# Quad_FC_V10_0.net
KiCad netlist of a schematic drawn in Altium Designer
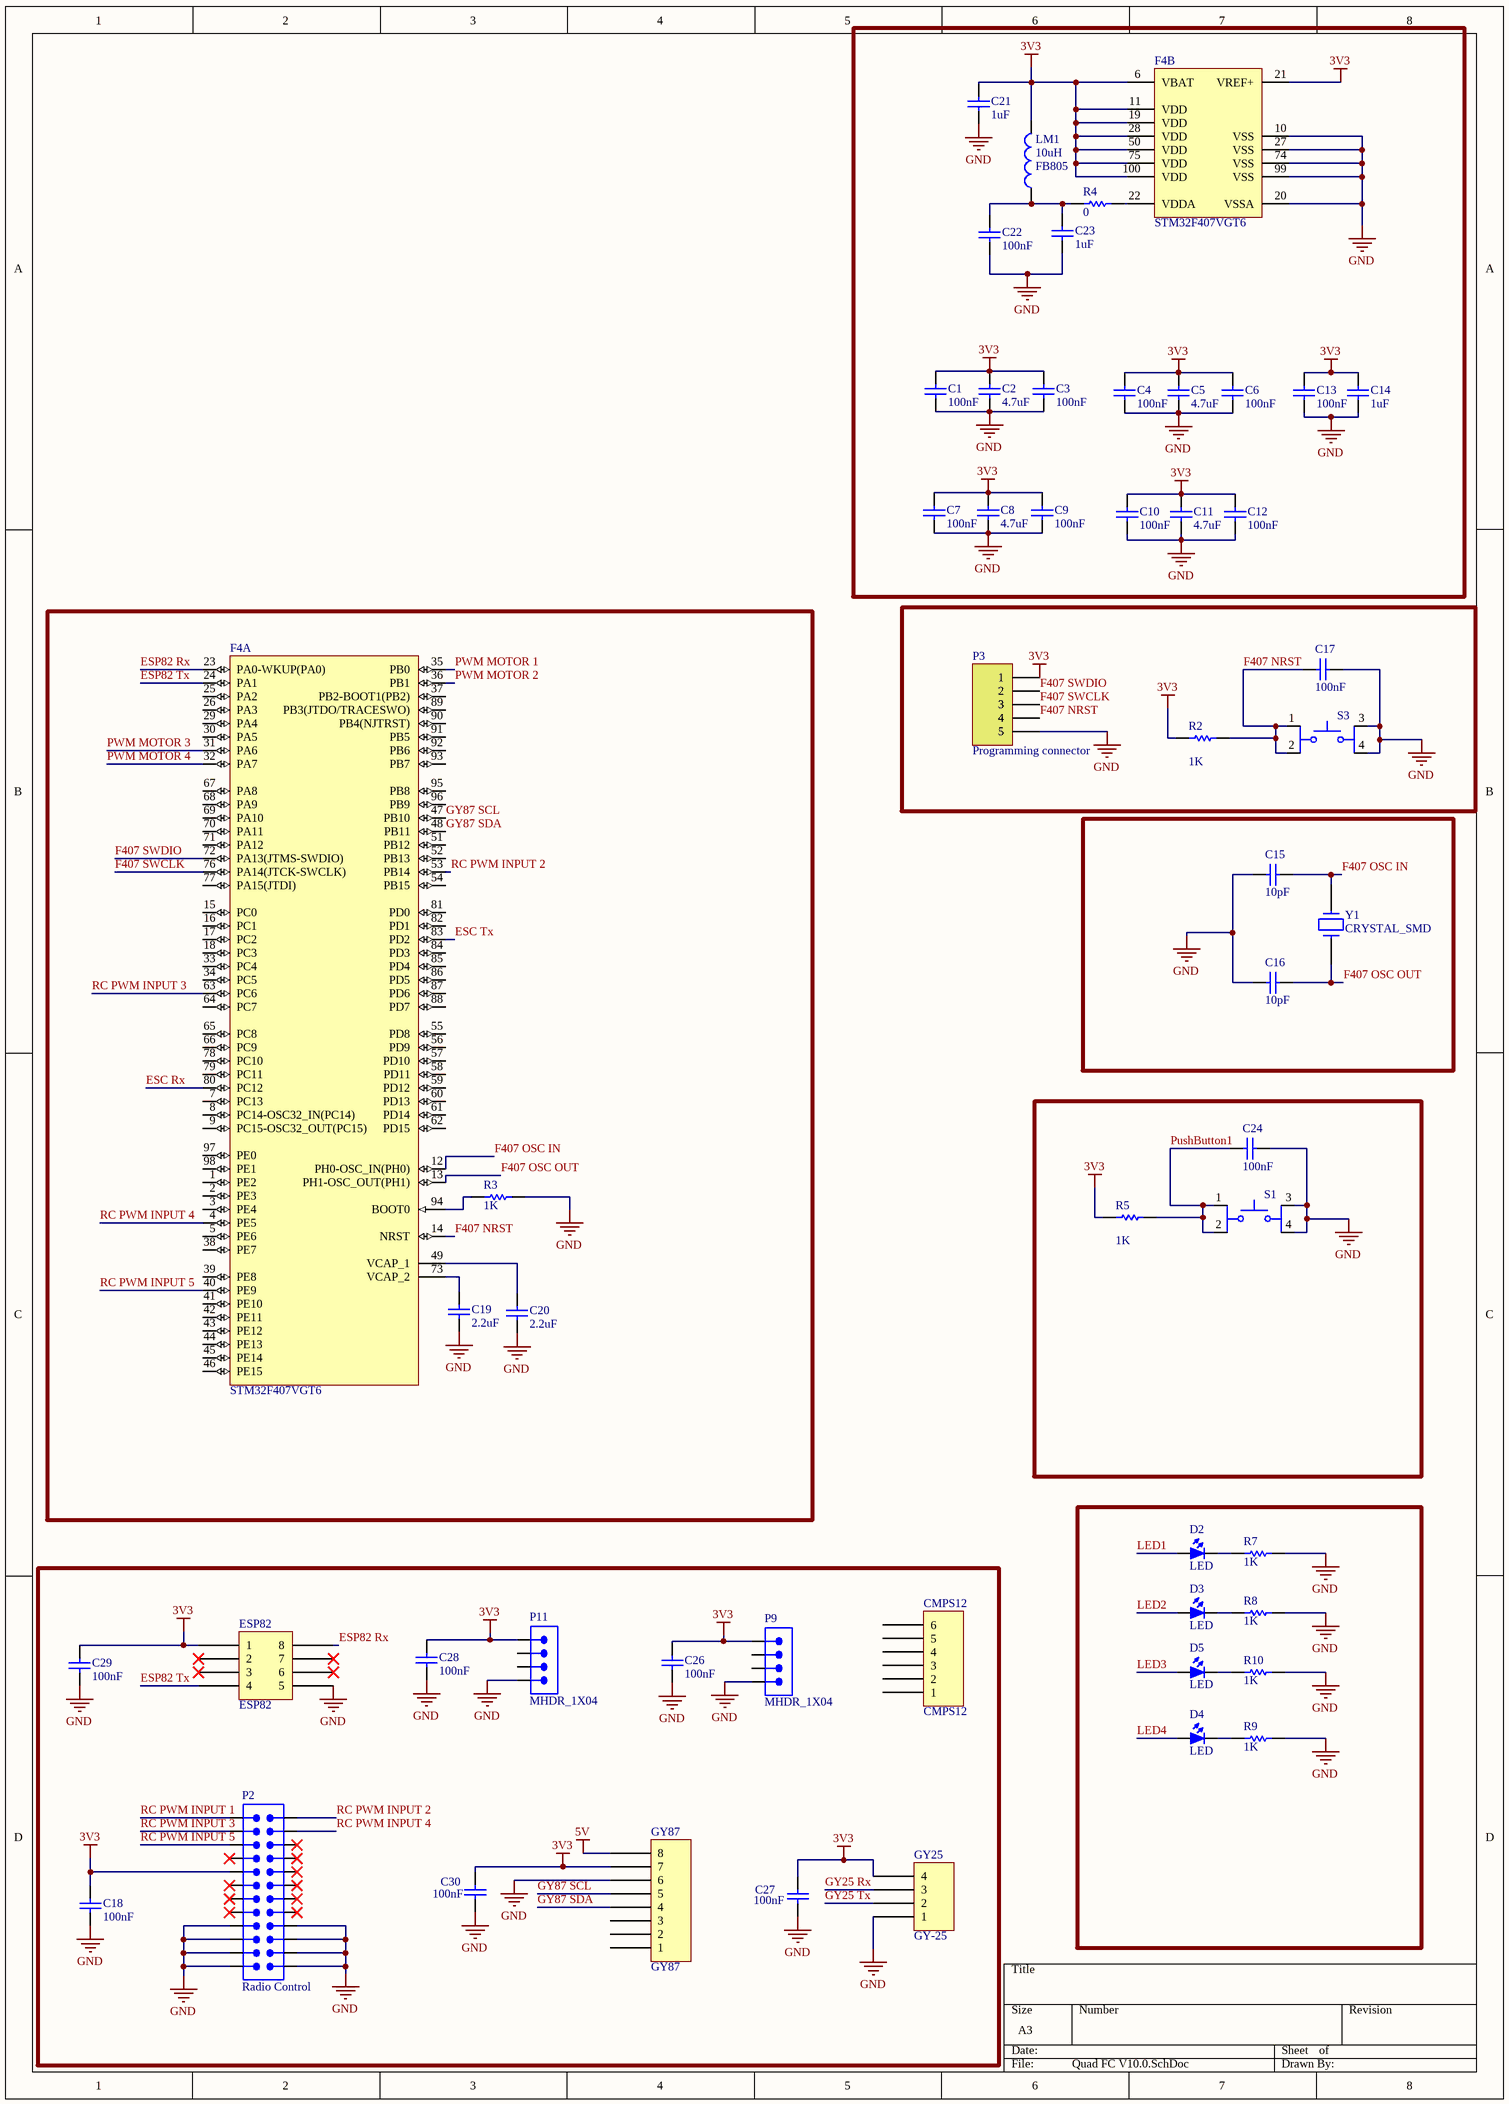
[diagram p0: Quad FC V10.0.SchDoc]

(export (version "E")
  (design (tool "Eeschema 10.0.6"))
  (components
    (comp (ref "C1")
      (value "100nF")
      (footprint "CAP0603")
      (description "F407VET6 Power CAP")
      (fields (field (name "DESIGNER") "Abbas Basereh"))
      (libsource (lib "2017AbbasBasereh9365731239 -ver1") (part "CAP SMD PACKAGE"))
    )
    (comp (ref "C2")
      (value "4.7uF")
      (footprint "CAP0603")
      (description "F407VET6 Power CAP")
      (fields (field (name "DESIGNER") "Abbas Basereh"))
      (libsource (lib "2017AbbasBasereh9365731239 -ver1") (part "CAP SMD PACKAGE"))
    )
    (comp (ref "C3")
      (value "100nF")
      (footprint "CAP0603")
      (description "F407VET6 Power CAP")
      (fields (field (name "DESIGNER") "Abbas Basereh"))
      (libsource (lib "2017AbbasBasereh9365731239 -ver1") (part "CAP SMD PACKAGE"))
    )
    (comp (ref "C4")
      (value "100nF")
      (footprint "CAP0603")
      (description "F407VET6 Power CAP")
      (fields (field (name "DESIGNER") "Abbas Basereh"))
      (libsource (lib "2017AbbasBasereh9365731239 -ver1") (part "CAP SMD PACKAGE"))
    )
    (comp (ref "C5")
      (value "4.7uF")
      (footprint "CAP0603")
      (description "F407VET6 Power CAP")
      (fields (field (name "DESIGNER") "Abbas Basereh"))
      (libsource (lib "2017AbbasBasereh9365731239 -ver1") (part "CAP SMD PACKAGE"))
    )
    (comp (ref "C6")
      (value "100nF")
      (footprint "CAP0603")
      (description "F407VET6 Power CAP")
      (fields (field (name "DESIGNER") "Abbas Basereh"))
      (libsource (lib "2017AbbasBasereh9365731239 -ver1") (part "CAP SMD PACKAGE"))
    )
    (comp (ref "C7")
      (value "100nF")
      (footprint "CAP0603")
      (description "F407VET6 Power CAP")
      (fields (field (name "DESIGNER") "Abbas Basereh"))
      (libsource (lib "2017AbbasBasereh9365731239 -ver1") (part "CAP SMD PACKAGE"))
    )
    (comp (ref "C8")
      (value "4.7uF")
      (footprint "CAP0603")
      (description "F407VET6 Power CAP")
      (fields (field (name "DESIGNER") "Abbas Basereh"))
      (libsource (lib "2017AbbasBasereh9365731239 -ver1") (part "CAP SMD PACKAGE"))
    )
    (comp (ref "C9")
      (value "100nF")
      (footprint "CAP0603")
      (description "F407VET6 Power CAP")
      (fields (field (name "DESIGNER") "Abbas Basereh"))
      (libsource (lib "2017AbbasBasereh9365731239 -ver1") (part "CAP SMD PACKAGE"))
    )
    (comp (ref "C10")
      (value "100nF")
      (footprint "CAP0603")
      (description "F407VET6 Power CAP")
      (fields (field (name "DESIGNER") "Abbas Basereh"))
      (libsource (lib "2017AbbasBasereh9365731239 -ver1") (part "CAP SMD PACKAGE"))
    )
    (comp (ref "C11")
      (value "4.7uF")
      (footprint "CAP0603")
      (description "F407VET6 Power CAP")
      (fields (field (name "DESIGNER") "Abbas Basereh"))
      (libsource (lib "2017AbbasBasereh9365731239 -ver1") (part "CAP SMD PACKAGE"))
    )
    (comp (ref "C12")
      (value "100nF")
      (footprint "CAP0603")
      (description "F407VET6 Power CAP")
      (fields (field (name "DESIGNER") "Abbas Basereh"))
      (libsource (lib "2017AbbasBasereh9365731239 -ver1") (part "CAP SMD PACKAGE"))
    )
    (comp (ref "C13")
      (value "100nF")
      (footprint "CAP0603")
      (description "F407VET6 Power CAP")
      (fields (field (name "DESIGNER") "Abbas Basereh"))
      (libsource (lib "2017AbbasBasereh9365731239 -ver1") (part "CAP SMD PACKAGE"))
    )
    (comp (ref "C14")
      (value "1uF")
      (footprint "CAP0603")
      (description "F407VET6 Power CAP")
      (fields (field (name "DESIGNER") "Abbas Basereh"))
      (libsource (lib "2017AbbasBasereh9365731239 -ver1") (part "CAP SMD PACKAGE"))
    )
    (comp (ref "C15")
      (value "10pF")
      (footprint "CAP0603")
      (description "F407VET6 Power CAP")
      (fields (field (name "DESIGNER") "Abbas Basereh"))
      (libsource (lib "2017AbbasBasereh9365731239 -ver1") (part "CAP SMD PACKAGE"))
    )
    (comp (ref "C16")
      (value "10pF")
      (footprint "CAP0603")
      (description "F407VET6 Power CAP")
      (fields (field (name "DESIGNER") "Abbas Basereh"))
      (libsource (lib "2017AbbasBasereh9365731239 -ver1") (part "CAP SMD PACKAGE"))
    )
    (comp (ref "C17")
      (value "100nF")
      (footprint "CAP0603")
      (description "F407VET6 Power CAP")
      (fields (field (name "DESIGNER") "Abbas Basereh"))
      (libsource (lib "2017AbbasBasereh9365731239 -ver1") (part "CAP SMD PACKAGE"))
    )
    (comp (ref "C18")
      (value "100nF")
      (footprint "CAP0603")
      (description "F407VET6 Power CAP")
      (fields (field (name "DESIGNER") "Abbas Basereh"))
      (libsource (lib "2017AbbasBasereh9365731239 -ver1") (part "CAP SMD PACKAGE"))
    )
    (comp (ref "C19")
      (value "2.2uF")
      (footprint "CAP0603")
      (description "F407VET6 Power CAP")
      (fields (field (name "DESIGNER") "Abbas Basereh"))
      (libsource (lib "2017AbbasBasereh9365731239 -ver1") (part "CAP SMD PACKAGE"))
    )
    (comp (ref "C20")
      (value "2.2uF")
      (footprint "CAP0603")
      (description "F407VET6 Power CAP")
      (fields (field (name "DESIGNER") "Abbas Basereh"))
      (libsource (lib "2017AbbasBasereh9365731239 -ver1") (part "CAP SMD PACKAGE"))
    )
    (comp (ref "C21")
      (value "1uF")
      (footprint "CAP0603")
      (description "F407VET6 Power CAP")
      (fields (field (name "DESIGNER") "Abbas Basereh"))
      (libsource (lib "2017AbbasBasereh9365731239 -ver1") (part "CAP SMD PACKAGE"))
    )
    (comp (ref "C22")
      (value "100nF")
      (footprint "CAP0603")
      (description "F407VET6 Power CAP")
      (fields (field (name "DESIGNER") "Abbas Basereh"))
      (libsource (lib "2017AbbasBasereh9365731239 -ver1") (part "CAP SMD PACKAGE"))
    )
    (comp (ref "C23")
      (value "1uF")
      (footprint "CAP0603")
      (description "F407VET6 Power CAP")
      (fields (field (name "DESIGNER") "Abbas Basereh"))
      (libsource (lib "2017AbbasBasereh9365731239 -ver1") (part "CAP SMD PACKAGE"))
    )
    (comp (ref "C24")
      (value "100nF")
      (footprint "CAP0603")
      (description "F407VET6 Power CAP")
      (fields (field (name "DESIGNER") "Abbas Basereh"))
      (libsource (lib "2017AbbasBasereh9365731239 -ver1") (part "CAP SMD PACKAGE"))
    )
    (comp (ref "C26")
      (value "100nF")
      (footprint "CAP0603")
      (description "F407VET6 Power CAP")
      (fields (field (name "DESIGNER") "Abbas Basereh"))
      (libsource (lib "2017AbbasBasereh9365731239 -ver1") (part "CAP SMD PACKAGE"))
    )
    (comp (ref "C27")
      (value "100nF")
      (footprint "CAP0603")
      (description "F407VET6 Power CAP")
      (fields (field (name "DESIGNER") "Abbas Basereh"))
      (libsource (lib "2017AbbasBasereh9365731239 -ver1") (part "CAP SMD PACKAGE"))
    )
    (comp (ref "C28")
      (value "100nF")
      (footprint "CAP0603")
      (description "F407VET6 Power CAP")
      (fields (field (name "DESIGNER") "Abbas Basereh"))
      (libsource (lib "2017AbbasBasereh9365731239 -ver1") (part "CAP SMD PACKAGE"))
    )
    (comp (ref "C29")
      (value "100nF")
      (footprint "CAP0603")
      (description "F407VET6 Power CAP")
      (fields (field (name "DESIGNER") "Abbas Basereh"))
      (libsource (lib "2017AbbasBasereh9365731239 -ver1") (part "CAP SMD PACKAGE"))
    )
    (comp (ref "C30")
      (value "100nF")
      (footprint "CAP0603")
      (description "F407VET6 Power CAP")
      (fields (field (name "DESIGNER") "Abbas Basereh"))
      (libsource (lib "2017AbbasBasereh9365731239 -ver1") (part "CAP SMD PACKAGE"))
    )
    (comp (ref "CMPS12")
      (value "CMPS12")
      (footprint "SULLINS NPPN061BFCN")
      (description "CONN HDR 6POS 0.079 GOLD PCB")
      (fields
        (field (name "PART NUMBER") "NPPN061BFCN-RC")
        (field (name "MANUFACTURER") "Sullins Connector Solutions")
      )
      (libsource (lib "Celestial Altium Library - altium_library (1)") (part "6 Pin"))
    )
    (comp (ref "D2")
      (value "LED")
      (footprint "0603 - LED")
      (description "Led")
      (fields (field (name "PUBLISHER") "Altium Limited"))
      (libsource (lib "Sajad_Altium_Library") (part "LED"))
    )
    (comp (ref "D3")
      (value "LED")
      (footprint "0603 - LED")
      (description "Led")
      (fields (field (name "PUBLISHER") "Altium Limited"))
      (libsource (lib "Sajad_Altium_Library") (part "LED"))
    )
    (comp (ref "D4")
      (value "LED")
      (footprint "0603 - LED")
      (description "Led")
      (fields (field (name "PUBLISHER") "Altium Limited"))
      (libsource (lib "Sajad_Altium_Library") (part "LED"))
    )
    (comp (ref "D5")
      (value "LED")
      (footprint "0603 - LED")
      (description "Led")
      (fields (field (name "PUBLISHER") "Altium Limited"))
      (libsource (lib "Sajad_Altium_Library") (part "LED"))
    )
    (comp (ref "ESP82")
      (value "ESP82")
      (footprint "HARWIN M20-7830445")
      (description "CONN RCPT 8POS 0.1 GOLD PCB")
      (fields (field (name "PART NUMBER") "M20-7830442") (field (name "MANUFACTURER") "Harwin Inc."))
      (libsource (lib "Celestial Altium Library - altium_library (1)") (part "2X4 PIN DU"))
    )
    (comp (ref "F4")
      (value "STM32F407VGT6")
      (footprint "STM-LQFP100_N")
      (fields (field (name "MANUFACTURER") "STMicroelectronics"))
      (libsource (lib "STMicroelectronics STM32 F4") (part "STM32F407VGT6"))
    )
    (comp (ref "GY25")
      (value "GY-25")
      (footprint "SULLINS NPPN041BFCN")
      (description "CONN HDR 4POS 0.079 GOLD PCB")
      (fields
        (field (name "PART NUMBER") "NPPN041BFCN-RC")
        (field (name "MANUFACTURER") "Sullins Connector Solutions")
      )
      (libsource (lib "Celestial Altium Library - altium_library (1)") (part "4 Pin"))
    )
    (comp (ref "GY87")
      (value "GY87")
      (footprint "SULLINS NPPN081BFCN")
      (description "CONN HDR 8POS 0.079 GOLD PCB")
      (fields
        (field (name "PART NUMBER") "NPPN081BFCN-RC")
        (field (name "MANUFACTURER") "Sullins Connector Solutions")
      )
      (libsource (lib "Celestial Altium Library - altium_library (1)") (part "8 Pin"))
    )
    (comp (ref "LM1")
      (value "10uH")
      (footprint "0805L")
      (description "Inductor")
      (fields (field (name "ALTIUM_VALUE") "FB805") (field (name "PUBLISHER") "Altium Limited"))
      (libsource (lib "2017AbbasBasereh9365731239 -ver1") (part "L SMA 0.25W"))
    )
    (comp (ref "P2")
      (value "Radio Control")
      (footprint "HEADER8X3:HEADER8X3")
      (description "Male Header 2X12")
      (libsource (lib "SJ Sockets & Connectors") (part "MHDR_2X12"))
    )
    (comp (ref "P3")
      (value "Programming connector")
      (footprint "Connector1X5")
      (description "Connector, 5-Pin2.5mm")
      (fields (field (name "PUBLISHER") "Altium Limited"))
      (libsource (lib "Sajad_Altium_Library") (part "Connector1x5"))
    )
    (comp (ref "P9")
      (value "MHDR_1X04")
      (footprint "JST BM04B-SURS-TF")
      (description "Male Header 1X04")
      (libsource (lib "SJ Sockets & Connectors") (part "MHDR_1X04"))
    )
    (comp (ref "P11")
      (value "MHDR_1X04")
      (footprint "JST BM04B-SURS-TF")
      (description "Male Header 1X04")
      (libsource (lib "SJ Sockets & Connectors") (part "MHDR_1X04"))
    )
    (comp (ref "R2")
      (value "1K")
      (footprint "RES0603")
      (description "TOTAL SMD RESISTOR PACK")
      (fields (field (name "DESIGNER") "Abbas Basereh"))
      (libsource (lib "2017AbbasBasereh9365731239 -ver1") (part "RES SMD PACKAGE"))
    )
    (comp (ref "R3")
      (value "1K")
      (footprint "RES0603")
      (description "TOTAL SMD RESISTOR PACK")
      (fields (field (name "DESIGNER") "Abbas Basereh"))
      (libsource (lib "2017AbbasBasereh9365731239 -ver1") (part "RES SMD PACKAGE"))
    )
    (comp (ref "R4")
      (value "0")
      (footprint "RES0603")
      (description "TOTAL SMD RESISTOR PACK")
      (fields (field (name "DESIGNER") "Abbas Basereh"))
      (libsource (lib "2017AbbasBasereh9365731239 -ver1") (part "RES SMD PACKAGE"))
    )
    (comp (ref "R5")
      (value "1K")
      (footprint "RES0603")
      (description "TOTAL SMD RESISTOR PACK")
      (fields (field (name "DESIGNER") "Abbas Basereh"))
      (libsource (lib "2017AbbasBasereh9365731239 -ver1") (part "RES SMD PACKAGE"))
    )
    (comp (ref "R7")
      (value "1K")
      (footprint "RES0603")
      (description "TOTAL SMD RESISTOR PACK")
      (fields (field (name "DESIGNER") "Abbas Basereh"))
      (libsource (lib "2017AbbasBasereh9365731239 -ver1") (part "RES SMD PACKAGE"))
    )
    (comp (ref "R8")
      (value "1K")
      (footprint "RES0603")
      (description "TOTAL SMD RESISTOR PACK")
      (fields (field (name "DESIGNER") "Abbas Basereh"))
      (libsource (lib "2017AbbasBasereh9365731239 -ver1") (part "RES SMD PACKAGE"))
    )
    (comp (ref "R9")
      (value "1K")
      (footprint "RES0603")
      (description "TOTAL SMD RESISTOR PACK")
      (fields (field (name "DESIGNER") "Abbas Basereh"))
      (libsource (lib "2017AbbasBasereh9365731239 -ver1") (part "RES SMD PACKAGE"))
    )
    (comp (ref "R10")
      (value "1K")
      (footprint "RES0603")
      (description "TOTAL SMD RESISTOR PACK")
      (fields (field (name "DESIGNER") "Abbas Basereh"))
      (libsource (lib "2017AbbasBasereh9365731239 -ver1") (part "RES SMD PACKAGE"))
    )
    (comp (ref "S1")
      (value "~")
      (footprint "SW_TL3301FF160QG")
      (description "Tactile switch for manual RESET")
      (fields (field (name "MF") "E-Switch") (field (name "MP") "TL3301FF160QG"))
      (libsource (lib "Tactile switch 6x6") (part "TL3301FF160QG"))
    )
    (comp (ref "S3")
      (value "~")
      (footprint "SW_TL3301FF160QG")
      (description "Tactile switch for manual RESET")
      (fields (field (name "MF") "E-Switch") (field (name "MP") "TL3301FF160QG"))
      (libsource (lib "Tactile switch 6x6") (part "TL3301FF160QG"))
    )
    (comp (ref "Y1")
      (value "CRYSTAL_SMD")
      (footprint "My_Crystal - SMD")
      (description "Crystal")
      (libsource (lib "AMINLIB") (part "CRYSTAL_SMD"))
    )
  )
  (nets
    (net (code "1") (name "/ESC Rx") (class "Default")
      (node (ref "F4") (pin "80") (pinfunction "PC12_80") (pintype "bidirectional"))
    )
    (net (code "2") (name "/ESC Tx") (class "Default")
      (node (ref "F4") (pin "83") (pinfunction "PD2_83") (pintype "bidirectional"))
    )
    (net (code "3") (name "/ESP82 Rx") (class "Default")
      (node (ref "ESP82") (pin "8") (pinfunction "8_8") (pintype "passive"))
      (node (ref "F4") (pin "23") (pinfunction "PA0-WKUP(PA0)_23") (pintype "bidirectional"))
    )
    (net (code "4") (name "/ESP82 Tx") (class "Default")
      (node (ref "ESP82") (pin "4") (pinfunction "4_4") (pintype "passive"))
      (node (ref "F4") (pin "24") (pinfunction "PA1_24") (pintype "bidirectional"))
    )
    (net (code "5") (name "/F407 NRST") (class "Default")
      (node (ref "C17") (pin "1") (pinfunction "1_1") (pintype "passive"))
      (node (ref "F4") (pin "14") (pinfunction "NRST_14") (pintype "bidirectional"))
      (node (ref "P3") (pin "4") (pinfunction "4_4") (pintype "passive"))
      (node (ref "R2") (pin "2") (pinfunction "2_2") (pintype "passive"))
      (node (ref "S3") (pin "1") (pinfunction "1_1") (pintype "passive"))
      (node (ref "S3") (pin "2") (pinfunction "2_2") (pintype "passive"))
    )
    (net (code "6") (name "/F407 OSC IN") (class "Default")
      (node (ref "C15") (pin "2") (pinfunction "2_2") (pintype "passive"))
      (node (ref "F4") (pin "12") (pinfunction "PH0-OSC_IN(PH0)_12") (pintype "bidirectional"))
      (node (ref "Y1") (pin "2") (pinfunction "2_2") (pintype "passive"))
    )
    (net (code "7") (name "/F407 OSC OUT") (class "Default")
      (node (ref "C16") (pin "1") (pinfunction "1_1") (pintype "passive"))
      (node (ref "F4") (pin "13") (pinfunction "PH1-OSC_OUT(PH1)_13") (pintype "bidirectional"))
      (node (ref "Y1") (pin "1") (pinfunction "1_1") (pintype "passive"))
    )
    (net (code "8") (name "/F407 SWCLK") (class "Default")
      (node (ref "F4") (pin "76") (pinfunction "PA14(JTCK-SWCLK)_76") (pintype "bidirectional"))
      (node (ref "P3") (pin "3") (pinfunction "3_3") (pintype "passive"))
    )
    (net (code "9") (name "/F407 SWDIO") (class "Default")
      (node (ref "F4") (pin "72") (pinfunction "PA13(JTMS-SWDIO)_72") (pintype "bidirectional"))
      (node (ref "P3") (pin "2") (pinfunction "2_2") (pintype "passive"))
    )
    (net (code "10") (name "/GY25 Rx") (class "Default")
      (node (ref "GY25") (pin "3") (pinfunction "3_3") (pintype "passive"))
    )
    (net (code "11") (name "/GY25 Tx") (class "Default")
      (node (ref "GY25") (pin "2") (pinfunction "2_2") (pintype "passive"))
    )
    (net (code "12") (name "/GY87 SCL") (class "Default")
      (node (ref "F4") (pin "47") (pinfunction "PB10_47") (pintype "bidirectional"))
      (node (ref "GY87") (pin "5") (pinfunction "5_5") (pintype "passive"))
    )
    (net (code "13") (name "/GY87 SDA") (class "Default")
      (node (ref "F4") (pin "48") (pinfunction "PB11_48") (pintype "bidirectional"))
      (node (ref "GY87") (pin "4") (pinfunction "4_4") (pintype "passive"))
    )
    (net (code "14") (name "/LED1") (class "Default")
      (node (ref "D2") (pin "1") (pinfunction "A_1") (pintype "passive"))
    )
    (net (code "15") (name "/LED2") (class "Default")
      (node (ref "D3") (pin "1") (pinfunction "A_1") (pintype "passive"))
    )
    (net (code "16") (name "/LED3") (class "Default")
      (node (ref "D5") (pin "1") (pinfunction "A_1") (pintype "passive"))
    )
    (net (code "17") (name "/LED4") (class "Default")
      (node (ref "D4") (pin "1") (pinfunction "A_1") (pintype "passive"))
    )
    (net (code "18") (name "/PWM MOTOR 1") (class "Default")
      (node (ref "F4") (pin "35") (pinfunction "PB0_35") (pintype "bidirectional"))
    )
    (net (code "19") (name "/PWM MOTOR 2") (class "Default")
      (node (ref "F4") (pin "36") (pinfunction "PB1_36") (pintype "bidirectional"))
    )
    (net (code "20") (name "/PWM MOTOR 3") (class "Default")
      (node (ref "F4") (pin "31") (pinfunction "PA6_31") (pintype "bidirectional"))
    )
    (net (code "21") (name "/PWM MOTOR 4") (class "Default")
      (node (ref "F4") (pin "32") (pinfunction "PA7_32") (pintype "bidirectional"))
    )
    (net (code "22") (name "/PushButton1") (class "Default")
      (node (ref "C24") (pin "1") (pinfunction "1_1") (pintype "passive"))
      (node (ref "R5") (pin "2") (pinfunction "2_2") (pintype "passive"))
      (node (ref "S1") (pin "1") (pinfunction "1_1") (pintype "passive"))
      (node (ref "S1") (pin "2") (pinfunction "2_2") (pintype "passive"))
    )
    (net (code "23") (name "/RC PWM INPUT 1") (class "Default")
      (node (ref "P2") (pin "1") (pinfunction "1_1") (pintype "passive"))
    )
    (net (code "24") (name "/RC PWM INPUT 2") (class "Default")
      (node (ref "F4") (pin "53") (pinfunction "PB14_53") (pintype "bidirectional"))
      (node (ref "P2") (pin "2") (pinfunction "2_2") (pintype "passive"))
    )
    (net (code "25") (name "/RC PWM INPUT 3") (class "Default")
      (node (ref "F4") (pin "63") (pinfunction "PC6_63") (pintype "bidirectional"))
      (node (ref "P2") (pin "3") (pinfunction "3_3") (pintype "passive"))
    )
    (net (code "26") (name "/RC PWM INPUT 4") (class "Default")
      (node (ref "F4") (pin "4") (pinfunction "PE5_4") (pintype "bidirectional"))
      (node (ref "P2") (pin "4") (pinfunction "4_4") (pintype "passive"))
    )
    (net (code "27") (name "/RC PWM INPUT 5") (class "Default")
      (node (ref "F4") (pin "40") (pinfunction "PE9_40") (pintype "bidirectional"))
      (node (ref "P2") (pin "5") (pinfunction "5_5") (pintype "passive"))
    )
    (net (code "28") (name "3V3") (class "Default")
      (node (ref "C1") (pin "2") (pinfunction "2_2") (pintype "passive"))
      (node (ref "C10") (pin "2") (pinfunction "2_2") (pintype "passive"))
      (node (ref "C11") (pin "2") (pinfunction "2_2") (pintype "passive"))
      (node (ref "C12") (pin "2") (pinfunction "2_2") (pintype "passive"))
      (node (ref "C13") (pin "1") (pinfunction "1_1") (pintype "passive"))
      (node (ref "C14") (pin "1") (pinfunction "1_1") (pintype "passive"))
      (node (ref "C18") (pin "1") (pinfunction "1_1") (pintype "passive"))
      (node (ref "C2") (pin "2") (pinfunction "2_2") (pintype "passive"))
      (node (ref "C21") (pin "2") (pinfunction "2_2") (pintype "passive"))
      (node (ref "C26") (pin "1") (pinfunction "1_1") (pintype "passive"))
      (node (ref "C27") (pin "1") (pinfunction "1_1") (pintype "passive"))
      (node (ref "C28") (pin "1") (pinfunction "1_1") (pintype "passive"))
      (node (ref "C29") (pin "1") (pinfunction "1_1") (pintype "passive"))
      (node (ref "C3") (pin "2") (pinfunction "2_2") (pintype "passive"))
      (node (ref "C30") (pin "2") (pinfunction "2_2") (pintype "passive"))
      (node (ref "C4") (pin "2") (pinfunction "2_2") (pintype "passive"))
      (node (ref "C5") (pin "2") (pinfunction "2_2") (pintype "passive"))
      (node (ref "C6") (pin "2") (pinfunction "2_2") (pintype "passive"))
      (node (ref "C7") (pin "2") (pinfunction "2_2") (pintype "passive"))
      (node (ref "C8") (pin "2") (pinfunction "2_2") (pintype "passive"))
      (node (ref "C9") (pin "2") (pinfunction "2_2") (pintype "passive"))
      (node (ref "ESP82") (pin "1") (pinfunction "1_1") (pintype "passive"))
      (node (ref "F4") (pin "100") (pinfunction "VDD_100") (pintype "power_in"))
      (node (ref "F4") (pin "11") (pinfunction "VDD_11") (pintype "power_in"))
      (node (ref "F4") (pin "19") (pinfunction "VDD_19") (pintype "power_in"))
      (node (ref "F4") (pin "21") (pinfunction "VREF+_21") (pintype "power_in"))
      (node (ref "F4") (pin "28") (pinfunction "VDD_28") (pintype "power_in"))
      (node (ref "F4") (pin "50") (pinfunction "VDD_50") (pintype "power_in"))
      (node (ref "F4") (pin "6") (pinfunction "VBAT_6") (pintype "power_in"))
      (node (ref "F4") (pin "75") (pinfunction "VDD_75") (pintype "power_in"))
      (node (ref "GY25") (pin "4") (pinfunction "4_4") (pintype "passive"))
      (node (ref "GY87") (pin "7") (pinfunction "7_7") (pintype "passive"))
      (node (ref "LM1") (pin "2") (pinfunction "2_2") (pintype "passive"))
      (node (ref "P11") (pin "1") (pinfunction "1_1") (pintype "passive"))
      (node (ref "P2") (pin "9") (pinfunction "9_9") (pintype "passive"))
      (node (ref "P3") (pin "1") (pinfunction "1_1") (pintype "passive"))
      (node (ref "P9") (pin "1") (pinfunction "1_1") (pintype "passive"))
      (node (ref "R2") (pin "1") (pinfunction "1_1") (pintype "passive"))
      (node (ref "R5") (pin "1") (pinfunction "1_1") (pintype "passive"))
    )
    (net (code "29") (name "5V") (class "Default")
      (node (ref "GY87") (pin "8") (pinfunction "8_8") (pintype "passive"))
    )
    (net (code "30") (name "GND") (class "Default")
      (node (ref "C1") (pin "1") (pinfunction "1_1") (pintype "passive"))
      (node (ref "C10") (pin "1") (pinfunction "1_1") (pintype "passive"))
      (node (ref "C11") (pin "1") (pinfunction "1_1") (pintype "passive"))
      (node (ref "C12") (pin "1") (pinfunction "1_1") (pintype "passive"))
      (node (ref "C13") (pin "2") (pinfunction "2_2") (pintype "passive"))
      (node (ref "C14") (pin "2") (pinfunction "2_2") (pintype "passive"))
      (node (ref "C15") (pin "1") (pinfunction "1_1") (pintype "passive"))
      (node (ref "C16") (pin "2") (pinfunction "2_2") (pintype "passive"))
      (node (ref "C17") (pin "2") (pinfunction "2_2") (pintype "passive"))
      (node (ref "C18") (pin "2") (pinfunction "2_2") (pintype "passive"))
      (node (ref "C19") (pin "2") (pinfunction "2_2") (pintype "passive"))
      (node (ref "C2") (pin "1") (pinfunction "1_1") (pintype "passive"))
      (node (ref "C20") (pin "2") (pinfunction "2_2") (pintype "passive"))
      (node (ref "C21") (pin "1") (pinfunction "1_1") (pintype "passive"))
      (node (ref "C22") (pin "1") (pinfunction "1_1") (pintype "passive"))
      (node (ref "C23") (pin "1") (pinfunction "1_1") (pintype "passive"))
      (node (ref "C24") (pin "2") (pinfunction "2_2") (pintype "passive"))
      (node (ref "C26") (pin "2") (pinfunction "2_2") (pintype "passive"))
      (node (ref "C27") (pin "2") (pinfunction "2_2") (pintype "passive"))
      (node (ref "C28") (pin "2") (pinfunction "2_2") (pintype "passive"))
      (node (ref "C29") (pin "2") (pinfunction "2_2") (pintype "passive"))
      (node (ref "C3") (pin "1") (pinfunction "1_1") (pintype "passive"))
      (node (ref "C30") (pin "1") (pinfunction "1_1") (pintype "passive"))
      (node (ref "C4") (pin "1") (pinfunction "1_1") (pintype "passive"))
      (node (ref "C5") (pin "1") (pinfunction "1_1") (pintype "passive"))
      (node (ref "C6") (pin "1") (pinfunction "1_1") (pintype "passive"))
      (node (ref "C7") (pin "1") (pinfunction "1_1") (pintype "passive"))
      (node (ref "C8") (pin "1") (pinfunction "1_1") (pintype "passive"))
      (node (ref "C9") (pin "1") (pinfunction "1_1") (pintype "passive"))
      (node (ref "ESP82") (pin "5") (pinfunction "5_5") (pintype "passive"))
      (node (ref "F4") (pin "10") (pinfunction "VSS_10") (pintype "power_in"))
      (node (ref "F4") (pin "20") (pinfunction "VSSA_20") (pintype "power_in"))
      (node (ref "F4") (pin "27") (pinfunction "VSS_27") (pintype "power_in"))
      (node (ref "F4") (pin "74") (pinfunction "VSS_74") (pintype "power_in"))
      (node (ref "F4") (pin "99") (pinfunction "VSS_99") (pintype "power_in"))
      (node (ref "GY25") (pin "1") (pinfunction "1_1") (pintype "passive"))
      (node (ref "GY87") (pin "6") (pinfunction "6_6") (pintype "passive"))
      (node (ref "P11") (pin "4") (pinfunction "4_4") (pintype "passive"))
      (node (ref "P2") (pin "17") (pinfunction "17_17") (pintype "passive"))
      (node (ref "P2") (pin "18") (pinfunction "18_18") (pintype "passive"))
      (node (ref "P2") (pin "19") (pinfunction "19_19") (pintype "passive"))
      (node (ref "P2") (pin "20") (pinfunction "20_20") (pintype "passive"))
      (node (ref "P2") (pin "21") (pinfunction "21_21") (pintype "passive"))
      (node (ref "P2") (pin "22") (pinfunction "22_22") (pintype "passive"))
      (node (ref "P2") (pin "23") (pinfunction "23_23") (pintype "passive"))
      (node (ref "P2") (pin "24") (pinfunction "24_24") (pintype "passive"))
      (node (ref "P3") (pin "5") (pinfunction "5_5") (pintype "passive"))
      (node (ref "P9") (pin "4") (pinfunction "4_4") (pintype "passive"))
      (node (ref "R10") (pin "2") (pinfunction "2_2") (pintype "passive"))
      (node (ref "R3") (pin "2") (pinfunction "2_2") (pintype "passive"))
      (node (ref "R7") (pin "2") (pinfunction "2_2") (pintype "passive"))
      (node (ref "R8") (pin "2") (pinfunction "2_2") (pintype "passive"))
      (node (ref "R9") (pin "2") (pinfunction "2_2") (pintype "passive"))
      (node (ref "S1") (pin "3") (pinfunction "3_3") (pintype "passive"))
      (node (ref "S1") (pin "4") (pinfunction "4_4") (pintype "passive"))
      (node (ref "S3") (pin "3") (pinfunction "3_3") (pintype "passive"))
      (node (ref "S3") (pin "4") (pinfunction "4_4") (pintype "passive"))
    )
    (net (code "31") (name "Net-(C22-Pad2)") (class "Default")
      (node (ref "C22") (pin "2") (pinfunction "2_2") (pintype "passive"))
      (node (ref "C23") (pin "2") (pinfunction "2_2") (pintype "passive"))
      (node (ref "LM1") (pin "1") (pinfunction "1_1") (pintype "passive"))
      (node (ref "R4") (pin "1") (pinfunction "1_1") (pintype "passive"))
    )
    (net (code "32") (name "Net-(D2-K)") (class "Default")
      (node (ref "D2") (pin "2") (pinfunction "K_2") (pintype "passive"))
      (node (ref "R7") (pin "1") (pinfunction "1_1") (pintype "passive"))
    )
    (net (code "33") (name "Net-(D3-K)") (class "Default")
      (node (ref "D3") (pin "2") (pinfunction "K_2") (pintype "passive"))
      (node (ref "R8") (pin "1") (pinfunction "1_1") (pintype "passive"))
    )
    (net (code "34") (name "Net-(D4-K)") (class "Default")
      (node (ref "D4") (pin "2") (pinfunction "K_2") (pintype "passive"))
      (node (ref "R9") (pin "1") (pinfunction "1_1") (pintype "passive"))
    )
    (net (code "35") (name "Net-(D5-K)") (class "Default")
      (node (ref "D5") (pin "2") (pinfunction "K_2") (pintype "passive"))
      (node (ref "R10") (pin "1") (pinfunction "1_1") (pintype "passive"))
    )
    (net (code "36") (name "Net-(F4A-BOOT0)") (class "Default")
      (node (ref "F4") (pin "94") (pinfunction "BOOT0_94") (pintype "input"))
      (node (ref "R3") (pin "1") (pinfunction "1_1") (pintype "passive"))
    )
    (net (code "37") (name "Net-(F4A-VCAP_1)") (class "Default")
      (node (ref "C20") (pin "1") (pinfunction "1_1") (pintype "passive"))
      (node (ref "F4") (pin "49") (pinfunction "VCAP_1_49") (pintype "power_in"))
    )
    (net (code "38") (name "Net-(F4A-VCAP_2)") (class "Default")
      (node (ref "C19") (pin "1") (pinfunction "1_1") (pintype "passive"))
      (node (ref "F4") (pin "73") (pinfunction "VCAP_2_73") (pintype "power_in"))
    )
    (net (code "39") (name "Net-(F4B-VDDA)") (class "Default")
      (node (ref "F4") (pin "22") (pinfunction "VDDA_22") (pintype "power_in"))
      (node (ref "R4") (pin "2") (pinfunction "2_2") (pintype "passive"))
    )
    (net (code "40") (name "unconnected-(CMPS12-Pad1)") (class "Default")
      (node (ref "CMPS12") (pin "1") (pinfunction "1_1") (pintype "passive"))
    )
    (net (code "41") (name "unconnected-(CMPS12-Pad2)") (class "Default")
      (node (ref "CMPS12") (pin "2") (pinfunction "2_2") (pintype "passive"))
    )
    (net (code "42") (name "unconnected-(CMPS12-Pad3)") (class "Default")
      (node (ref "CMPS12") (pin "3") (pinfunction "3_3") (pintype "passive"))
    )
    (net (code "43") (name "unconnected-(CMPS12-Pad4)") (class "Default")
      (node (ref "CMPS12") (pin "4") (pinfunction "4_4") (pintype "passive"))
    )
    (net (code "44") (name "unconnected-(CMPS12-Pad5)") (class "Default")
      (node (ref "CMPS12") (pin "5") (pinfunction "5_5") (pintype "passive"))
    )
    (net (code "45") (name "unconnected-(CMPS12-Pad6)") (class "Default")
      (node (ref "CMPS12") (pin "6") (pinfunction "6_6") (pintype "passive"))
    )
    (net (code "46") (name "unconnected-(ESP82-Pad2)") (class "Default")
      (node (ref "ESP82") (pin "2") (pinfunction "2_2") (pintype "passive+no_connect"))
    )
    (net (code "47") (name "unconnected-(ESP82-Pad3)") (class "Default")
      (node (ref "ESP82") (pin "3") (pinfunction "3_3") (pintype "passive+no_connect"))
    )
    (net (code "48") (name "unconnected-(ESP82-Pad6)") (class "Default")
      (node (ref "ESP82") (pin "6") (pinfunction "6_6") (pintype "passive+no_connect"))
    )
    (net (code "49") (name "unconnected-(ESP82-Pad7)") (class "Default")
      (node (ref "ESP82") (pin "7") (pinfunction "7_7") (pintype "passive+no_connect"))
    )
    (net (code "50") (name "unconnected-(F4A-PA2-Pad25)") (class "Default")
      (node (ref "F4") (pin "25") (pinfunction "PA2_25") (pintype "bidirectional"))
    )
    (net (code "51") (name "unconnected-(F4A-PA3-Pad26)") (class "Default")
      (node (ref "F4") (pin "26") (pinfunction "PA3_26") (pintype "bidirectional"))
    )
    (net (code "52") (name "unconnected-(F4A-PA4-Pad29)") (class "Default")
      (node (ref "F4") (pin "29") (pinfunction "PA4_29") (pintype "bidirectional"))
    )
    (net (code "53") (name "unconnected-(F4A-PA5-Pad30)") (class "Default")
      (node (ref "F4") (pin "30") (pinfunction "PA5_30") (pintype "bidirectional"))
    )
    (net (code "54") (name "unconnected-(F4A-PA8-Pad67)") (class "Default")
      (node (ref "F4") (pin "67") (pinfunction "PA8_67") (pintype "bidirectional"))
    )
    (net (code "55") (name "unconnected-(F4A-PA9-Pad68)") (class "Default")
      (node (ref "F4") (pin "68") (pinfunction "PA9_68") (pintype "bidirectional"))
    )
    (net (code "56") (name "unconnected-(F4A-PA10-Pad69)") (class "Default")
      (node (ref "F4") (pin "69") (pinfunction "PA10_69") (pintype "bidirectional"))
    )
    (net (code "57") (name "unconnected-(F4A-PA11-Pad70)") (class "Default")
      (node (ref "F4") (pin "70") (pinfunction "PA11_70") (pintype "bidirectional"))
    )
    (net (code "58") (name "unconnected-(F4A-PA12-Pad71)") (class "Default")
      (node (ref "F4") (pin "71") (pinfunction "PA12_71") (pintype "bidirectional"))
    )
    (net (code "59") (name "unconnected-(F4A-PA15(JTDI)-Pad77)") (class "Default")
      (node (ref "F4") (pin "77") (pinfunction "PA15(JTDI)_77") (pintype "bidirectional"))
    )
    (net (code "60") (name "unconnected-(F4A-PB2-BOOT1(PB2)-Pad37)") (class "Default")
      (node (ref "F4") (pin "37") (pinfunction "PB2-BOOT1(PB2)_37") (pintype "bidirectional"))
    )
    (net (code "61") (name "unconnected-(F4A-PB3(JTDO{slash}TRACESWO)-Pad89)") (class "Default")
      (node (ref "F4") (pin "89") (pinfunction "PB3(JTDO/TRACESWO)_89") (pintype "bidirectional"))
    )
    (net (code "62") (name "unconnected-(F4A-PB4(NJTRST)-Pad90)") (class "Default")
      (node (ref "F4") (pin "90") (pinfunction "PB4(NJTRST)_90") (pintype "bidirectional"))
    )
    (net (code "63") (name "unconnected-(F4A-PB5-Pad91)") (class "Default")
      (node (ref "F4") (pin "91") (pinfunction "PB5_91") (pintype "bidirectional"))
    )
    (net (code "64") (name "unconnected-(F4A-PB6-Pad92)") (class "Default")
      (node (ref "F4") (pin "92") (pinfunction "PB6_92") (pintype "bidirectional"))
    )
    (net (code "65") (name "unconnected-(F4A-PB7-Pad93)") (class "Default")
      (node (ref "F4") (pin "93") (pinfunction "PB7_93") (pintype "bidirectional"))
    )
    (net (code "66") (name "unconnected-(F4A-PB8-Pad95)") (class "Default")
      (node (ref "F4") (pin "95") (pinfunction "PB8_95") (pintype "bidirectional"))
    )
    (net (code "67") (name "unconnected-(F4A-PB9-Pad96)") (class "Default")
      (node (ref "F4") (pin "96") (pinfunction "PB9_96") (pintype "bidirectional"))
    )
    (net (code "68") (name "unconnected-(F4A-PB12-Pad51)") (class "Default")
      (node (ref "F4") (pin "51") (pinfunction "PB12_51") (pintype "bidirectional"))
    )
    (net (code "69") (name "unconnected-(F4A-PB13-Pad52)") (class "Default")
      (node (ref "F4") (pin "52") (pinfunction "PB13_52") (pintype "bidirectional"))
    )
    (net (code "70") (name "unconnected-(F4A-PB15-Pad54)") (class "Default")
      (node (ref "F4") (pin "54") (pinfunction "PB15_54") (pintype "bidirectional"))
    )
    (net (code "71") (name "unconnected-(F4A-PC0-Pad15)") (class "Default")
      (node (ref "F4") (pin "15") (pinfunction "PC0_15") (pintype "bidirectional"))
    )
    (net (code "72") (name "unconnected-(F4A-PC1-Pad16)") (class "Default")
      (node (ref "F4") (pin "16") (pinfunction "PC1_16") (pintype "bidirectional"))
    )
    (net (code "73") (name "unconnected-(F4A-PC2-Pad17)") (class "Default")
      (node (ref "F4") (pin "17") (pinfunction "PC2_17") (pintype "bidirectional"))
    )
    (net (code "74") (name "unconnected-(F4A-PC3-Pad18)") (class "Default")
      (node (ref "F4") (pin "18") (pinfunction "PC3_18") (pintype "bidirectional"))
    )
    (net (code "75") (name "unconnected-(F4A-PC4-Pad33)") (class "Default")
      (node (ref "F4") (pin "33") (pinfunction "PC4_33") (pintype "bidirectional"))
    )
    (net (code "76") (name "unconnected-(F4A-PC5-Pad34)") (class "Default")
      (node (ref "F4") (pin "34") (pinfunction "PC5_34") (pintype "bidirectional"))
    )
    (net (code "77") (name "unconnected-(F4A-PC7-Pad64)") (class "Default")
      (node (ref "F4") (pin "64") (pinfunction "PC7_64") (pintype "bidirectional"))
    )
    (net (code "78") (name "unconnected-(F4A-PC8-Pad65)") (class "Default")
      (node (ref "F4") (pin "65") (pinfunction "PC8_65") (pintype "bidirectional"))
    )
    (net (code "79") (name "unconnected-(F4A-PC9-Pad66)") (class "Default")
      (node (ref "F4") (pin "66") (pinfunction "PC9_66") (pintype "bidirectional"))
    )
    (net (code "80") (name "unconnected-(F4A-PC10-Pad78)") (class "Default")
      (node (ref "F4") (pin "78") (pinfunction "PC10_78") (pintype "bidirectional"))
    )
    (net (code "81") (name "unconnected-(F4A-PC11-Pad79)") (class "Default")
      (node (ref "F4") (pin "79") (pinfunction "PC11_79") (pintype "bidirectional"))
    )
    (net (code "82") (name "unconnected-(F4A-PC13-Pad7)") (class "Default")
      (node (ref "F4") (pin "7") (pinfunction "PC13_7") (pintype "bidirectional"))
    )
    (net (code "83") (name "unconnected-(F4A-PC14-OSC32_IN(PC14)-Pad8)") (class "Default")
      (node (ref "F4") (pin "8") (pinfunction "PC14-OSC32_IN(PC14)_8") (pintype "bidirectional"))
    )
    (net (code "84") (name "unconnected-(F4A-PC15-OSC32_OUT(PC15)-Pad9)") (class "Default")
      (node (ref "F4") (pin "9") (pinfunction "PC15-OSC32_OUT(PC15)_9") (pintype "bidirectional"))
    )
    (net (code "85") (name "unconnected-(F4A-PD0-Pad81)") (class "Default")
      (node (ref "F4") (pin "81") (pinfunction "PD0_81") (pintype "bidirectional"))
    )
    (net (code "86") (name "unconnected-(F4A-PD1-Pad82)") (class "Default")
      (node (ref "F4") (pin "82") (pinfunction "PD1_82") (pintype "bidirectional"))
    )
    (net (code "87") (name "unconnected-(F4A-PD3-Pad84)") (class "Default")
      (node (ref "F4") (pin "84") (pinfunction "PD3_84") (pintype "bidirectional"))
    )
    (net (code "88") (name "unconnected-(F4A-PD4-Pad85)") (class "Default")
      (node (ref "F4") (pin "85") (pinfunction "PD4_85") (pintype "bidirectional"))
    )
    (net (code "89") (name "unconnected-(F4A-PD5-Pad86)") (class "Default")
      (node (ref "F4") (pin "86") (pinfunction "PD5_86") (pintype "bidirectional"))
    )
    (net (code "90") (name "unconnected-(F4A-PD6-Pad87)") (class "Default")
      (node (ref "F4") (pin "87") (pinfunction "PD6_87") (pintype "bidirectional"))
    )
    (net (code "91") (name "unconnected-(F4A-PD7-Pad88)") (class "Default")
      (node (ref "F4") (pin "88") (pinfunction "PD7_88") (pintype "bidirectional"))
    )
    (net (code "92") (name "unconnected-(F4A-PD8-Pad55)") (class "Default")
      (node (ref "F4") (pin "55") (pinfunction "PD8_55") (pintype "bidirectional"))
    )
    (net (code "93") (name "unconnected-(F4A-PD9-Pad56)") (class "Default")
      (node (ref "F4") (pin "56") (pinfunction "PD9_56") (pintype "bidirectional"))
    )
    (net (code "94") (name "unconnected-(F4A-PD10-Pad57)") (class "Default")
      (node (ref "F4") (pin "57") (pinfunction "PD10_57") (pintype "bidirectional"))
    )
    (net (code "95") (name "unconnected-(F4A-PD11-Pad58)") (class "Default")
      (node (ref "F4") (pin "58") (pinfunction "PD11_58") (pintype "bidirectional"))
    )
    (net (code "96") (name "unconnected-(F4A-PD12-Pad59)") (class "Default")
      (node (ref "F4") (pin "59") (pinfunction "PD12_59") (pintype "bidirectional"))
    )
    (net (code "97") (name "unconnected-(F4A-PD13-Pad60)") (class "Default")
      (node (ref "F4") (pin "60") (pinfunction "PD13_60") (pintype "bidirectional"))
    )
    (net (code "98") (name "unconnected-(F4A-PD14-Pad61)") (class "Default")
      (node (ref "F4") (pin "61") (pinfunction "PD14_61") (pintype "bidirectional"))
    )
    (net (code "99") (name "unconnected-(F4A-PD15-Pad62)") (class "Default")
      (node (ref "F4") (pin "62") (pinfunction "PD15_62") (pintype "bidirectional"))
    )
    (net (code "100") (name "unconnected-(F4A-PE0-Pad97)") (class "Default")
      (node (ref "F4") (pin "97") (pinfunction "PE0_97") (pintype "bidirectional"))
    )
    (net (code "101") (name "unconnected-(F4A-PE1-Pad98)") (class "Default")
      (node (ref "F4") (pin "98") (pinfunction "PE1_98") (pintype "bidirectional"))
    )
    (net (code "102") (name "unconnected-(F4A-PE2-Pad1)") (class "Default")
      (node (ref "F4") (pin "1") (pinfunction "PE2_1") (pintype "bidirectional"))
    )
    (net (code "103") (name "unconnected-(F4A-PE3-Pad2)") (class "Default")
      (node (ref "F4") (pin "2") (pinfunction "PE3_2") (pintype "bidirectional"))
    )
    (net (code "104") (name "unconnected-(F4A-PE4-Pad3)") (class "Default")
      (node (ref "F4") (pin "3") (pinfunction "PE4_3") (pintype "bidirectional"))
    )
    (net (code "105") (name "unconnected-(F4A-PE6-Pad5)") (class "Default")
      (node (ref "F4") (pin "5") (pinfunction "PE6_5") (pintype "bidirectional"))
    )
    (net (code "106") (name "unconnected-(F4A-PE7-Pad38)") (class "Default")
      (node (ref "F4") (pin "38") (pinfunction "PE7_38") (pintype "bidirectional"))
    )
    (net (code "107") (name "unconnected-(F4A-PE8-Pad39)") (class "Default")
      (node (ref "F4") (pin "39") (pinfunction "PE8_39") (pintype "bidirectional"))
    )
    (net (code "108") (name "unconnected-(F4A-PE10-Pad41)") (class "Default")
      (node (ref "F4") (pin "41") (pinfunction "PE10_41") (pintype "bidirectional"))
    )
    (net (code "109") (name "unconnected-(F4A-PE11-Pad42)") (class "Default")
      (node (ref "F4") (pin "42") (pinfunction "PE11_42") (pintype "bidirectional"))
    )
    (net (code "110") (name "unconnected-(F4A-PE12-Pad43)") (class "Default")
      (node (ref "F4") (pin "43") (pinfunction "PE12_43") (pintype "bidirectional"))
    )
    (net (code "111") (name "unconnected-(F4A-PE13-Pad44)") (class "Default")
      (node (ref "F4") (pin "44") (pinfunction "PE13_44") (pintype "bidirectional"))
    )
    (net (code "112") (name "unconnected-(F4A-PE14-Pad45)") (class "Default")
      (node (ref "F4") (pin "45") (pinfunction "PE14_45") (pintype "bidirectional"))
    )
    (net (code "113") (name "unconnected-(F4A-PE15-Pad46)") (class "Default")
      (node (ref "F4") (pin "46") (pinfunction "PE15_46") (pintype "bidirectional"))
    )
    (net (code "114") (name "unconnected-(GY87-Pad1)") (class "Default")
      (node (ref "GY87") (pin "1") (pinfunction "1_1") (pintype "passive"))
    )
    (net (code "115") (name "unconnected-(GY87-Pad2)") (class "Default")
      (node (ref "GY87") (pin "2") (pinfunction "2_2") (pintype "passive"))
    )
    (net (code "116") (name "unconnected-(GY87-Pad3)") (class "Default")
      (node (ref "GY87") (pin "3") (pinfunction "3_3") (pintype "passive"))
    )
    (net (code "117") (name "unconnected-(P2-Pad6)") (class "Default")
      (node (ref "P2") (pin "6") (pinfunction "6_6") (pintype "passive+no_connect"))
    )
    (net (code "118") (name "unconnected-(P2-Pad7)") (class "Default")
      (node (ref "P2") (pin "7") (pinfunction "7_7") (pintype "passive+no_connect"))
    )
    (net (code "119") (name "unconnected-(P2-Pad8)") (class "Default")
      (node (ref "P2") (pin "8") (pinfunction "8_8") (pintype "passive+no_connect"))
    )
    (net (code "120") (name "unconnected-(P2-Pad10)") (class "Default")
      (node (ref "P2") (pin "10") (pinfunction "10_10") (pintype "passive+no_connect"))
    )
    (net (code "121") (name "unconnected-(P2-Pad11)") (class "Default")
      (node (ref "P2") (pin "11") (pinfunction "11_11") (pintype "passive+no_connect"))
    )
    (net (code "122") (name "unconnected-(P2-Pad12)") (class "Default")
      (node (ref "P2") (pin "12") (pinfunction "12_12") (pintype "passive+no_connect"))
    )
    (net (code "123") (name "unconnected-(P2-Pad13)") (class "Default")
      (node (ref "P2") (pin "13") (pinfunction "13_13") (pintype "passive+no_connect"))
    )
    (net (code "124") (name "unconnected-(P2-Pad14)") (class "Default")
      (node (ref "P2") (pin "14") (pinfunction "14_14") (pintype "passive+no_connect"))
    )
    (net (code "125") (name "unconnected-(P2-Pad15)") (class "Default")
      (node (ref "P2") (pin "15") (pinfunction "15_15") (pintype "passive+no_connect"))
    )
    (net (code "126") (name "unconnected-(P2-Pad16)") (class "Default")
      (node (ref "P2") (pin "16") (pinfunction "16_16") (pintype "passive+no_connect"))
    )
    (net (code "127") (name "unconnected-(P9-Pad2)") (class "Default")
      (node (ref "P9") (pin "2") (pinfunction "2_2") (pintype "passive"))
    )
    (net (code "128") (name "unconnected-(P9-Pad3)") (class "Default")
      (node (ref "P9") (pin "3") (pinfunction "3_3") (pintype "passive"))
    )
    (net (code "129") (name "unconnected-(P11-Pad2)") (class "Default")
      (node (ref "P11") (pin "2") (pinfunction "2_2") (pintype "passive"))
    )
    (net (code "130") (name "unconnected-(P11-Pad3)") (class "Default")
      (node (ref "P11") (pin "3") (pinfunction "3_3") (pintype "passive"))
    )
  )
)
